# 4V_DIST.net
KiCad netlist of a schematic drawn in Altium Designer
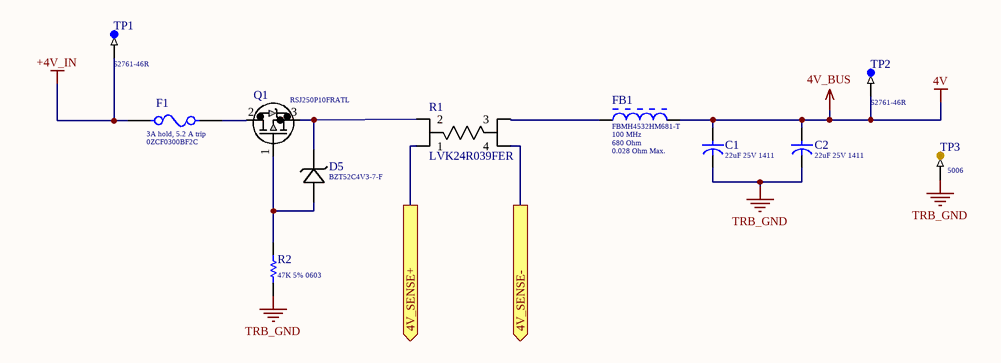
[diagram p0: 4V_DIST.SchDoc]

(export (version "E")
  (design (tool "Eeschema 10.0.6"))
  (components
    (comp (ref "C1")
      (value "Cap_Kemet_T521B226M025ATE100_22uF")
      (footprint "Cap_Kemet_T521B226M025ATE100_22uF")
      (description "Tantalum Capacitors - Polymer SMD 25V 22uF 1311 20% ESR=100mOhms")
      (fields (field (name "CAPACITANCE") "22uF 25V 1411"))
      (libsource (lib "Cap_Kemet_T521B226M025ATE100_22uF") (part "Cap_Kemet_T521B226M025ATE100_22uF"))
    )
    (comp (ref "C2")
      (value "Cap_Kemet_T521B226M025ATE100_22uF")
      (footprint "Cap_Kemet_T521B226M025ATE100_22uF")
      (description "Tantalum Capacitors - Polymer SMD 25V 22uF 1311 20% ESR=100mOhms")
      (fields (field (name "CAPACITANCE") "22uF 25V 1411"))
      (libsource (lib "Cap_Kemet_T521B226M025ATE100_22uF") (part "Cap_Kemet_T521B226M025ATE100_22uF"))
    )
    (comp (ref "D5")
      (value "BZT52C4V3-7-F")
      (footprint "SOD123")
      (description "Zener Diodes 500mW 4.3V Zener AEC-Q101 Qualified")
      (fields (field (name "SERIES") "BZT52C4V3-7-F"))
      (libsource (lib "4v3_zener_BZT52C4V3-7-F") (part "BZT52C4V3-7-F"))
    )
    (comp (ref "F1")
      (value "3A hold, 5.2 A trip")
      (footprint "Bel_0ZCF_MFG")
      (description "Resettable Fuses - PPTC 3A 24V PPTC 2920 SMD")
      (fields (field (name "SERIES") "0ZCF0300BF2C"))
      (libsource (lib "Fuse_Bel_0ZCF0300BF2C_3A_hold") (part "0ZCF0300BF2C"))
    )
    (comp (ref "FB1")
      (value "FBMH4532HM681-T")
      (footprint "TAYO-FBMH4532-2_V")
      (fields
        (field (name "PARTNUMBER") "FBMH4532HM681-T")
        (field (name "MANUFACTURER") "Taiyo Yuden")
        (field (name "MEASURING FREQUENCY") "100 MHz")
        (field (name "NOMINAL IMPEDANCE") "680 Ohm")
        (field (name "DC RESISTANCE") "0.028 Ohm Max.")
      )
      (libsource (lib "Taiyo_Yuden_FBMH4532HM681") (part "FBMH4532HM681-T"))
    )
    (comp (ref "Q1")
      (value "Mos_ROHM_RSJ250P10FRATL_25A")
      (footprint "Mos_ROHM_RSJ250P10FRATL_25A")
      (description "MOSFET Pch -100V Vds -25A 0.05Rds(on) 60Qg")
      (fields (field (name "SERIES") "RSJ250P10FRATL"))
      (libsource (lib "Mos_ROHM_RSJ250P10FRATL_25A") (part "Mos_ROHM_RSJ250P10FRATL_25A"))
    )
    (comp (ref "R1")
      (value "LVK24R039FER")
      (footprint "OH_LVK24_OHM")
      (description "RES 0.039 OHM 1% 1W 2412")
      (fields (field (name "COPYRIGHT") "Copyright (C) 2018 Accelerated Designs. All rights reserved"))
      (libsource (lib "Shunt_Res_Ohmite_LVK24R039FER") (part "LVK24R039FER"))
    )
    (comp (ref "R2")
      (value "47K 5% 0603")
      (footprint "RESC0603(1608)_L")
      (description "47K 0.1W 5% 0603 (1608 Metric)  SMD")
      (fields (field (name "TOLERANCE") "5 %") (field (name "POWER") "0.1 W"))
      (libsource (lib "Altium Content Vault") (part "RES"))
    )
    (comp (ref "TP1")
      (value "TP_Harwin_S2761_46R")
      (footprint "TP_Harwin_S2761_46R")
      (description "Circuit Board Hardware - PCB SMT Mini Test Terminal, Reel")
      (fields (field (name "SERIES") "S2761-46R"))
      (libsource (lib "TP_Harwin_S2761_46R") (part "TP_Harwin_S2761_46R"))
    )
    (comp (ref "TP2")
      (value "TP_Harwin_S2761_46R")
      (footprint "TP_Harwin_S2761_46R")
      (description "Circuit Board Hardware - PCB SMT Mini Test Terminal, Reel")
      (fields (field (name "SERIES") "S2761-46R"))
      (libsource (lib "TP_Harwin_S2761_46R") (part "TP_Harwin_S2761_46R"))
    )
    (comp (ref "TP3")
      (value "TP_Keystone_Electronics_5006")
      (footprint "TP_Keystone_Electronics_5006")
      (description "Circuit Board Hardware - PCB TEST POINT BLK .063")
      (fields (field (name "SERIES") "5006"))
      (libsource (lib "TP_Keystone_Electronics_5006") (part "TP_Keystone_Electronics_5006"))
    )
  )
  (nets
    (net (code "1") (name "+4V_IN") (class "Default")
      (node (ref "F1") (pin "1") (pinfunction "1_1") (pintype "passive"))
      (node (ref "TP1") (pin "1") (pinfunction "1_1") (pintype "input"))
    )
    (net (code "2") (name "/4V_SENSE+") (class "Default")
      (node (ref "R1") (pin "1") (pinfunction "1_1") (pintype "passive"))
    )
    (net (code "3") (name "/4V_SENSE-") (class "Default")
      (node (ref "R1") (pin "4") (pinfunction "4_4") (pintype "passive"))
    )
    (net (code "4") (name "4V") (class "Default")
      (node (ref "C1") (pin "1") (pinfunction "1_1") (pintype "passive"))
      (node (ref "C2") (pin "1") (pinfunction "1_1") (pintype "passive"))
      (node (ref "FB1") (pin "2") (pinfunction "2_2") (pintype "power_in"))
      (node (ref "TP2") (pin "1") (pinfunction "1_1") (pintype "input"))
    )
    (net (code "5") (name "Net-(FB1-Pad1)") (class "Default")
      (node (ref "FB1") (pin "1") (pinfunction "1_1") (pintype "power_in"))
      (node (ref "R1") (pin "3") (pinfunction "3_3") (pintype "power_in"))
    )
    (net (code "6") (name "Net-(Q1-D)") (class "Default")
      (node (ref "F1") (pin "2") (pinfunction "2_2") (pintype "passive"))
      (node (ref "Q1") (pin "2") (pinfunction "D_2") (pintype "power_in"))
    )
    (net (code "7") (name "Net-(Q1-G)") (class "Default")
      (node (ref "D5") (pin "2") (pinfunction "2_2") (pintype "passive"))
      (node (ref "Q1") (pin "1") (pinfunction "G_1") (pintype "passive"))
      (node (ref "R2") (pin "2") (pinfunction "2_2") (pintype "passive"))
    )
    (net (code "8") (name "Net-(Q1-S)") (class "Default")
      (node (ref "D5") (pin "1") (pinfunction "1_1") (pintype "passive"))
      (node (ref "Q1") (pin "3") (pinfunction "S_3") (pintype "power_in"))
      (node (ref "R1") (pin "2") (pinfunction "2_2") (pintype "power_in"))
    )
    (net (code "9") (name "TRB_GND") (class "Default")
      (node (ref "C1") (pin "2") (pinfunction "2_2") (pintype "passive"))
      (node (ref "C2") (pin "2") (pinfunction "2_2") (pintype "passive"))
      (node (ref "R2") (pin "1") (pinfunction "1_1") (pintype "passive"))
      (node (ref "TP3") (pin "1") (pinfunction "1_1") (pintype "input"))
    )
  )
)
